# Bant_Sayici.net
KiCad netlist of a schematic drawn in EAGLE
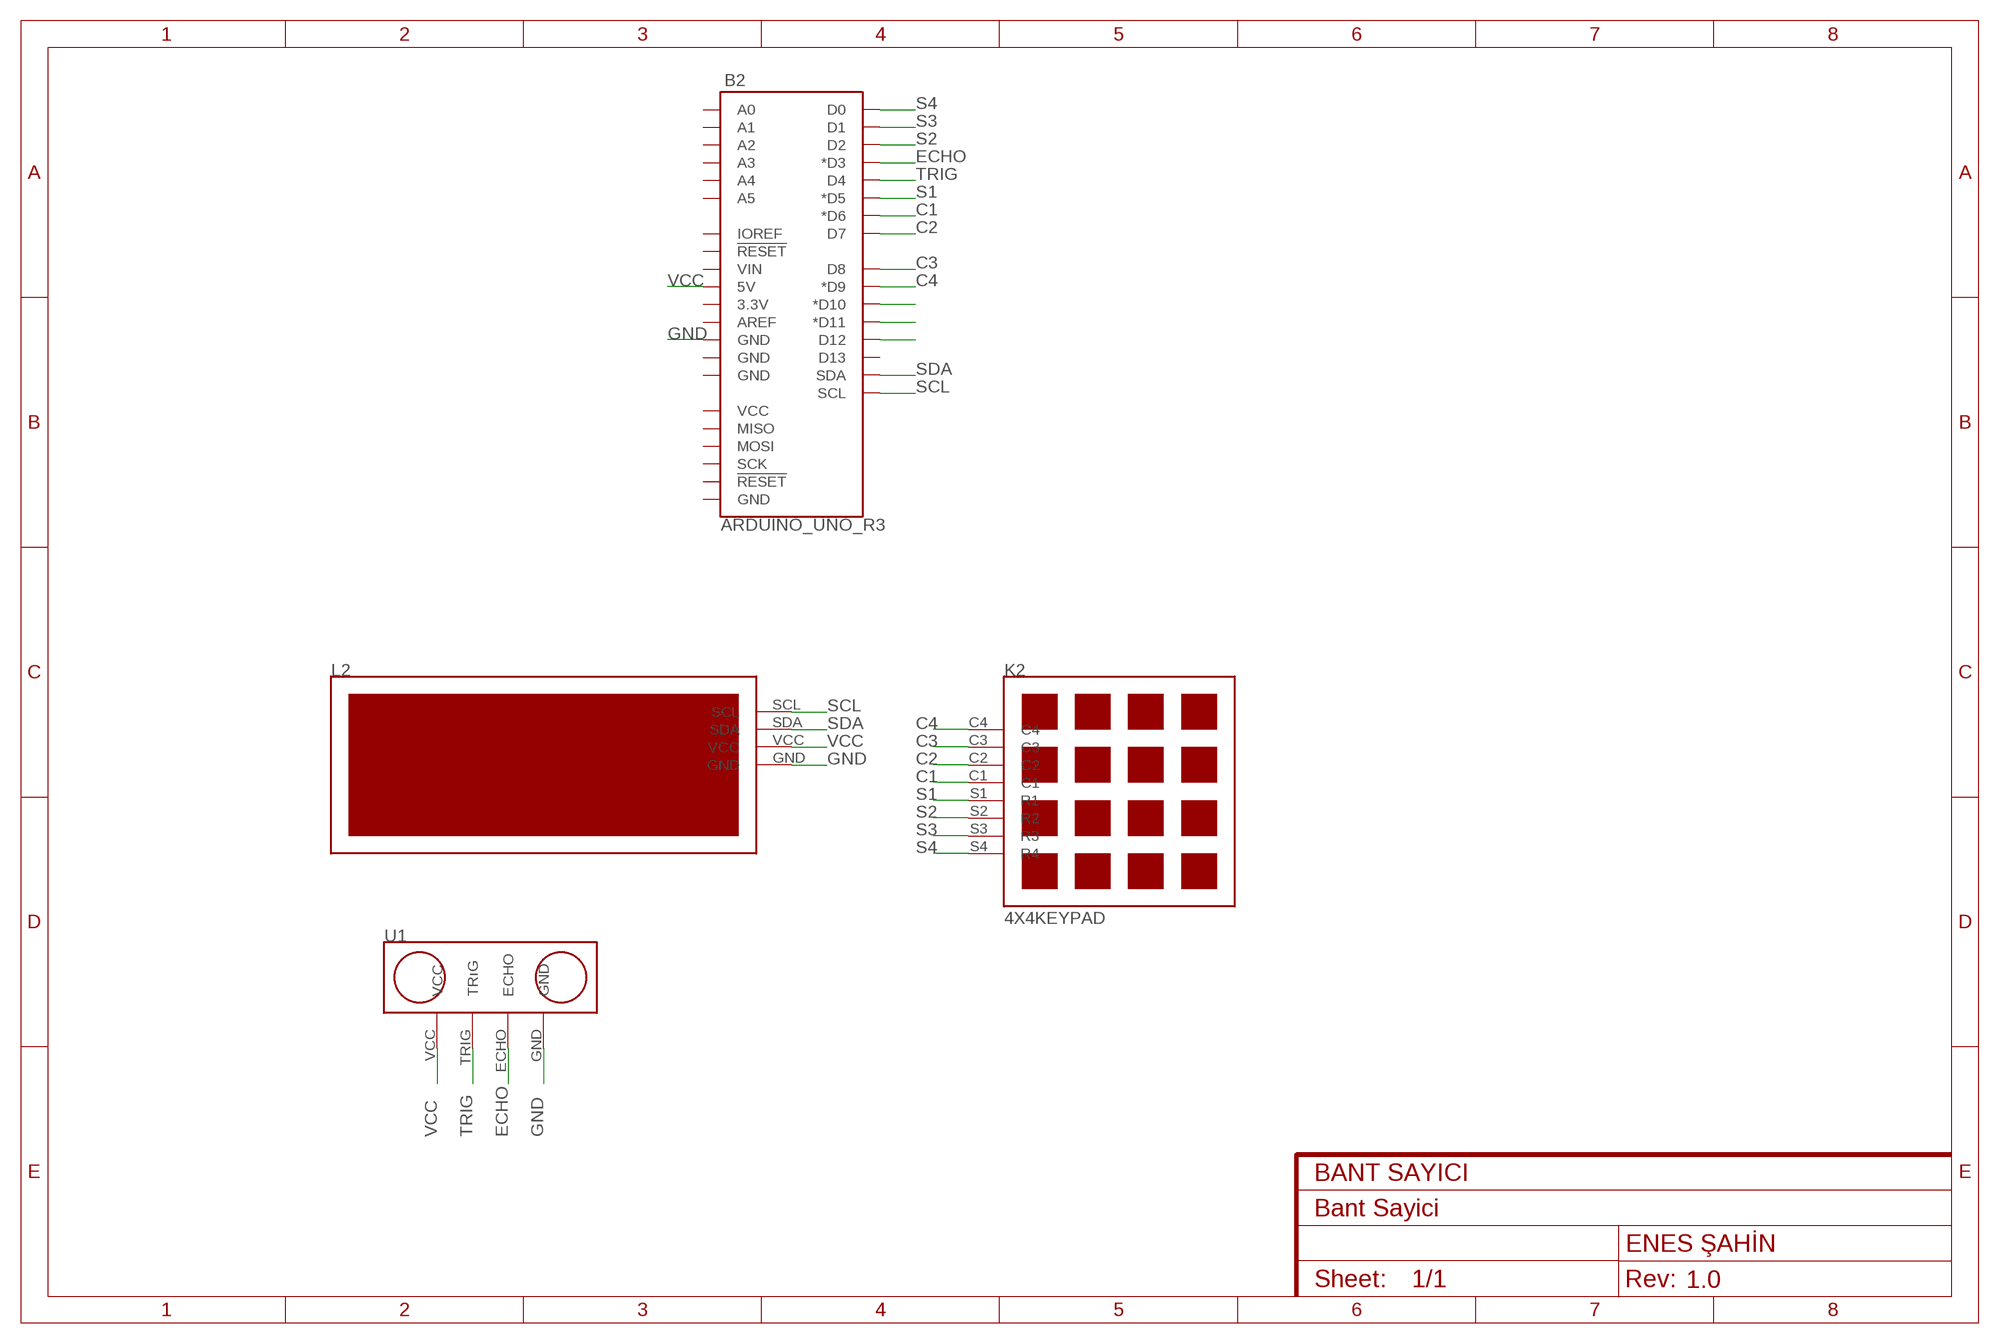
[diagram p0: schematic, sheet 1]

(export (version "E")
  (design (tool "Eeschema 10.0.6"))
  (components
    (comp (ref "B2")
      (value "ARDUINO_UNO_R3")
      (footprint "eagle-import:ARDUINO_R3")
      (libsource (lib "eagle-import") (part "ARDUINO_UNO_R3"))
    )
    (comp (ref "K2")
      (value "4X4KEYPAD")
      (footprint "eagle-import:4X4_KEYPAD")
      (libsource (lib "eagle-import") (part "4X4_KEYPAD"))
    )
    (comp (ref "L2")
      (value "16X2_LCD")
      (footprint "eagle-import:16X2_LCD")
      (libsource (lib "eagle-import") (part "16X2_LCD"))
    )
    (comp (ref "U1")
      (value "HCSR-04")
      (footprint "eagle-import:HCSR-04")
      (libsource (lib "eagle-import") (part "HCSR-04"))
    )
  )
  (nets
    (net (code "1") (name "/C1") (class "Default")
      (node (ref "B2") (pin "D6") (pinfunction "*D6_D6") (pintype "bidirectional"))
      (node (ref "K2") (pin "C1") (pinfunction "C1_C1") (pintype "bidirectional"))
    )
    (net (code "2") (name "/C2") (class "Default")
      (node (ref "B2") (pin "D7") (pinfunction "D7_D7") (pintype "bidirectional"))
      (node (ref "K2") (pin "C2") (pinfunction "C2_C2") (pintype "bidirectional"))
    )
    (net (code "3") (name "/C3") (class "Default")
      (node (ref "B2") (pin "D8") (pinfunction "D8_D8") (pintype "bidirectional"))
      (node (ref "K2") (pin "C3") (pinfunction "C3_C3") (pintype "bidirectional"))
    )
    (net (code "4") (name "/C4") (class "Default")
      (node (ref "B2") (pin "D9") (pinfunction "*D9_D9") (pintype "bidirectional"))
      (node (ref "K2") (pin "C4") (pinfunction "C4_C4") (pintype "bidirectional"))
    )
    (net (code "5") (name "/ECHO") (class "Default")
      (node (ref "B2") (pin "D3") (pinfunction "*D3_D3") (pintype "bidirectional"))
      (node (ref "U1") (pin "ECHO") (pinfunction "ECHO_ECHO") (pintype "bidirectional"))
    )
    (net (code "6") (name "/GND") (class "Default")
      (node (ref "B2") (pin "GND@4") (pinfunction "GND_GND@4") (pintype "bidirectional"))
      (node (ref "L2") (pin "GND") (pinfunction "GND_GND") (pintype "bidirectional"))
      (node (ref "U1") (pin "GND") (pinfunction "GND_GND") (pintype "bidirectional"))
    )
    (net (code "7") (name "/S1") (class "Default")
      (node (ref "B2") (pin "D5") (pinfunction "*D5_D5") (pintype "bidirectional"))
      (node (ref "K2") (pin "S1") (pinfunction "R1_S1") (pintype "bidirectional"))
    )
    (net (code "8") (name "/S2") (class "Default")
      (node (ref "B2") (pin "D2") (pinfunction "D2_D2") (pintype "bidirectional"))
      (node (ref "K2") (pin "S2") (pinfunction "R2_S2") (pintype "bidirectional"))
    )
    (net (code "9") (name "/S3") (class "Default")
      (node (ref "B2") (pin "D1") (pinfunction "D1_D1") (pintype "bidirectional"))
      (node (ref "K2") (pin "S3") (pinfunction "R3_S3") (pintype "bidirectional"))
    )
    (net (code "10") (name "/S4") (class "Default")
      (node (ref "B2") (pin "D0") (pinfunction "D0_D0") (pintype "bidirectional"))
      (node (ref "K2") (pin "S4") (pinfunction "R4_S4") (pintype "bidirectional"))
    )
    (net (code "11") (name "/SCL") (class "Default")
      (node (ref "B2") (pin "SCL") (pinfunction "SCL_SCL") (pintype "bidirectional"))
      (node (ref "L2") (pin "SCL") (pinfunction "SCL_SCL") (pintype "bidirectional"))
    )
    (net (code "12") (name "/SDA") (class "Default")
      (node (ref "B2") (pin "SDA") (pinfunction "SDA_SDA") (pintype "bidirectional"))
      (node (ref "L2") (pin "SDA") (pinfunction "SDA_SDA") (pintype "bidirectional"))
    )
    (net (code "13") (name "/TRIG") (class "Default")
      (node (ref "B2") (pin "D4") (pinfunction "D4_D4") (pintype "bidirectional"))
      (node (ref "U1") (pin "TRIG") (pinfunction "TRıG_TRIG") (pintype "bidirectional"))
    )
    (net (code "14") (name "/VCC") (class "Default")
      (node (ref "B2") (pin "5V") (pinfunction "5V_5V") (pintype "bidirectional"))
      (node (ref "L2") (pin "VCC") (pinfunction "VCC_VCC") (pintype "bidirectional"))
      (node (ref "U1") (pin "VCC") (pinfunction "VCC_VCC") (pintype "bidirectional"))
    )
    (net (code "15") (name "unconnected-(B2-*D10-PadD10)") (class "Default")
      (node (ref "B2") (pin "D10") (pinfunction "*D10_D10") (pintype "bidirectional"))
    )
    (net (code "16") (name "unconnected-(B2-*D11-PadD11)") (class "Default")
      (node (ref "B2") (pin "D11") (pinfunction "*D11_D11") (pintype "bidirectional"))
    )
    (net (code "17") (name "unconnected-(B2-GND-PadGND@1)") (class "Default")
      (node (ref "B2") (pin "GND@1") (pinfunction "GND_GND@1") (pintype "bidirectional"))
    )
    (net (code "18") (name "unconnected-(B2-GND-PadGND@2)") (class "Default")
      (node (ref "B2") (pin "GND@2") (pinfunction "GND_GND@2") (pintype "bidirectional"))
    )
    (net (code "19") (name "unconnected-(B2-GND-PadGND@3)") (class "Default")
      (node (ref "B2") (pin "GND@3") (pinfunction "GND_GND@3") (pintype "bidirectional"))
    )
    (net (code "20") (name "unconnected-(B2-Pad3.3V)") (class "Default")
      (node (ref "B2") (pin "3.3V") (pinfunction "3.3V_3.3V") (pintype "bidirectional"))
    )
    (net (code "21") (name "unconnected-(B2-PadA0)") (class "Default")
      (node (ref "B2") (pin "A0") (pinfunction "A0_A0") (pintype "bidirectional"))
    )
    (net (code "22") (name "unconnected-(B2-PadA1)") (class "Default")
      (node (ref "B2") (pin "A1") (pinfunction "A1_A1") (pintype "bidirectional"))
    )
    (net (code "23") (name "unconnected-(B2-PadA2)") (class "Default")
      (node (ref "B2") (pin "A2") (pinfunction "A2_A2") (pintype "bidirectional"))
    )
    (net (code "24") (name "unconnected-(B2-PadA3)") (class "Default")
      (node (ref "B2") (pin "A3") (pinfunction "A3_A3") (pintype "bidirectional"))
    )
    (net (code "25") (name "unconnected-(B2-PadA4)") (class "Default")
      (node (ref "B2") (pin "A4") (pinfunction "A4_A4") (pintype "bidirectional"))
    )
    (net (code "26") (name "unconnected-(B2-PadA5)") (class "Default")
      (node (ref "B2") (pin "A5") (pinfunction "A5_A5") (pintype "bidirectional"))
    )
    (net (code "27") (name "unconnected-(B2-PadAREF)") (class "Default")
      (node (ref "B2") (pin "AREF") (pinfunction "AREF_AREF") (pintype "bidirectional"))
    )
    (net (code "28") (name "unconnected-(B2-PadD12)") (class "Default")
      (node (ref "B2") (pin "D12") (pinfunction "D12_D12") (pintype "bidirectional"))
    )
    (net (code "29") (name "unconnected-(B2-PadD13)") (class "Default")
      (node (ref "B2") (pin "D13") (pinfunction "D13_D13") (pintype "bidirectional"))
    )
    (net (code "30") (name "unconnected-(B2-PadIOREF)") (class "Default")
      (node (ref "B2") (pin "IOREF") (pinfunction "IOREF_IOREF") (pintype "bidirectional"))
    )
    (net (code "31") (name "unconnected-(B2-PadMISO)") (class "Default")
      (node (ref "B2") (pin "MISO") (pinfunction "MISO_MISO") (pintype "bidirectional"))
    )
    (net (code "32") (name "unconnected-(B2-PadMOSI)") (class "Default")
      (node (ref "B2") (pin "MOSI") (pinfunction "MOSI_MOSI") (pintype "bidirectional"))
    )
    (net (code "33") (name "unconnected-(B2-PadSCK)") (class "Default")
      (node (ref "B2") (pin "SCK") (pinfunction "SCK_SCK") (pintype "bidirectional"))
    )
    (net (code "34") (name "unconnected-(B2-PadVCC)") (class "Default")
      (node (ref "B2") (pin "VCC") (pinfunction "VCC_VCC") (pintype "bidirectional"))
    )
    (net (code "35") (name "unconnected-(B2-PadVIN)") (class "Default")
      (node (ref "B2") (pin "VIN") (pinfunction "VIN_VIN") (pintype "bidirectional"))
    )
    (net (code "36") (name "unconnected-(B2-~{RESET}-PadRESET@1)") (class "Default")
      (node (ref "B2") (pin "RESET@1") (pinfunction "~{RESET}_RESET@1") (pintype "bidirectional"))
    )
    (net (code "37") (name "unconnected-(B2-~{RESET}-PadRESET@2)") (class "Default")
      (node (ref "B2") (pin "RESET@2") (pinfunction "~{RESET}_RESET@2") (pintype "bidirectional"))
    )
  )
)
